# design.net
KiCad netlist of a schematic drawn in Altium Designer
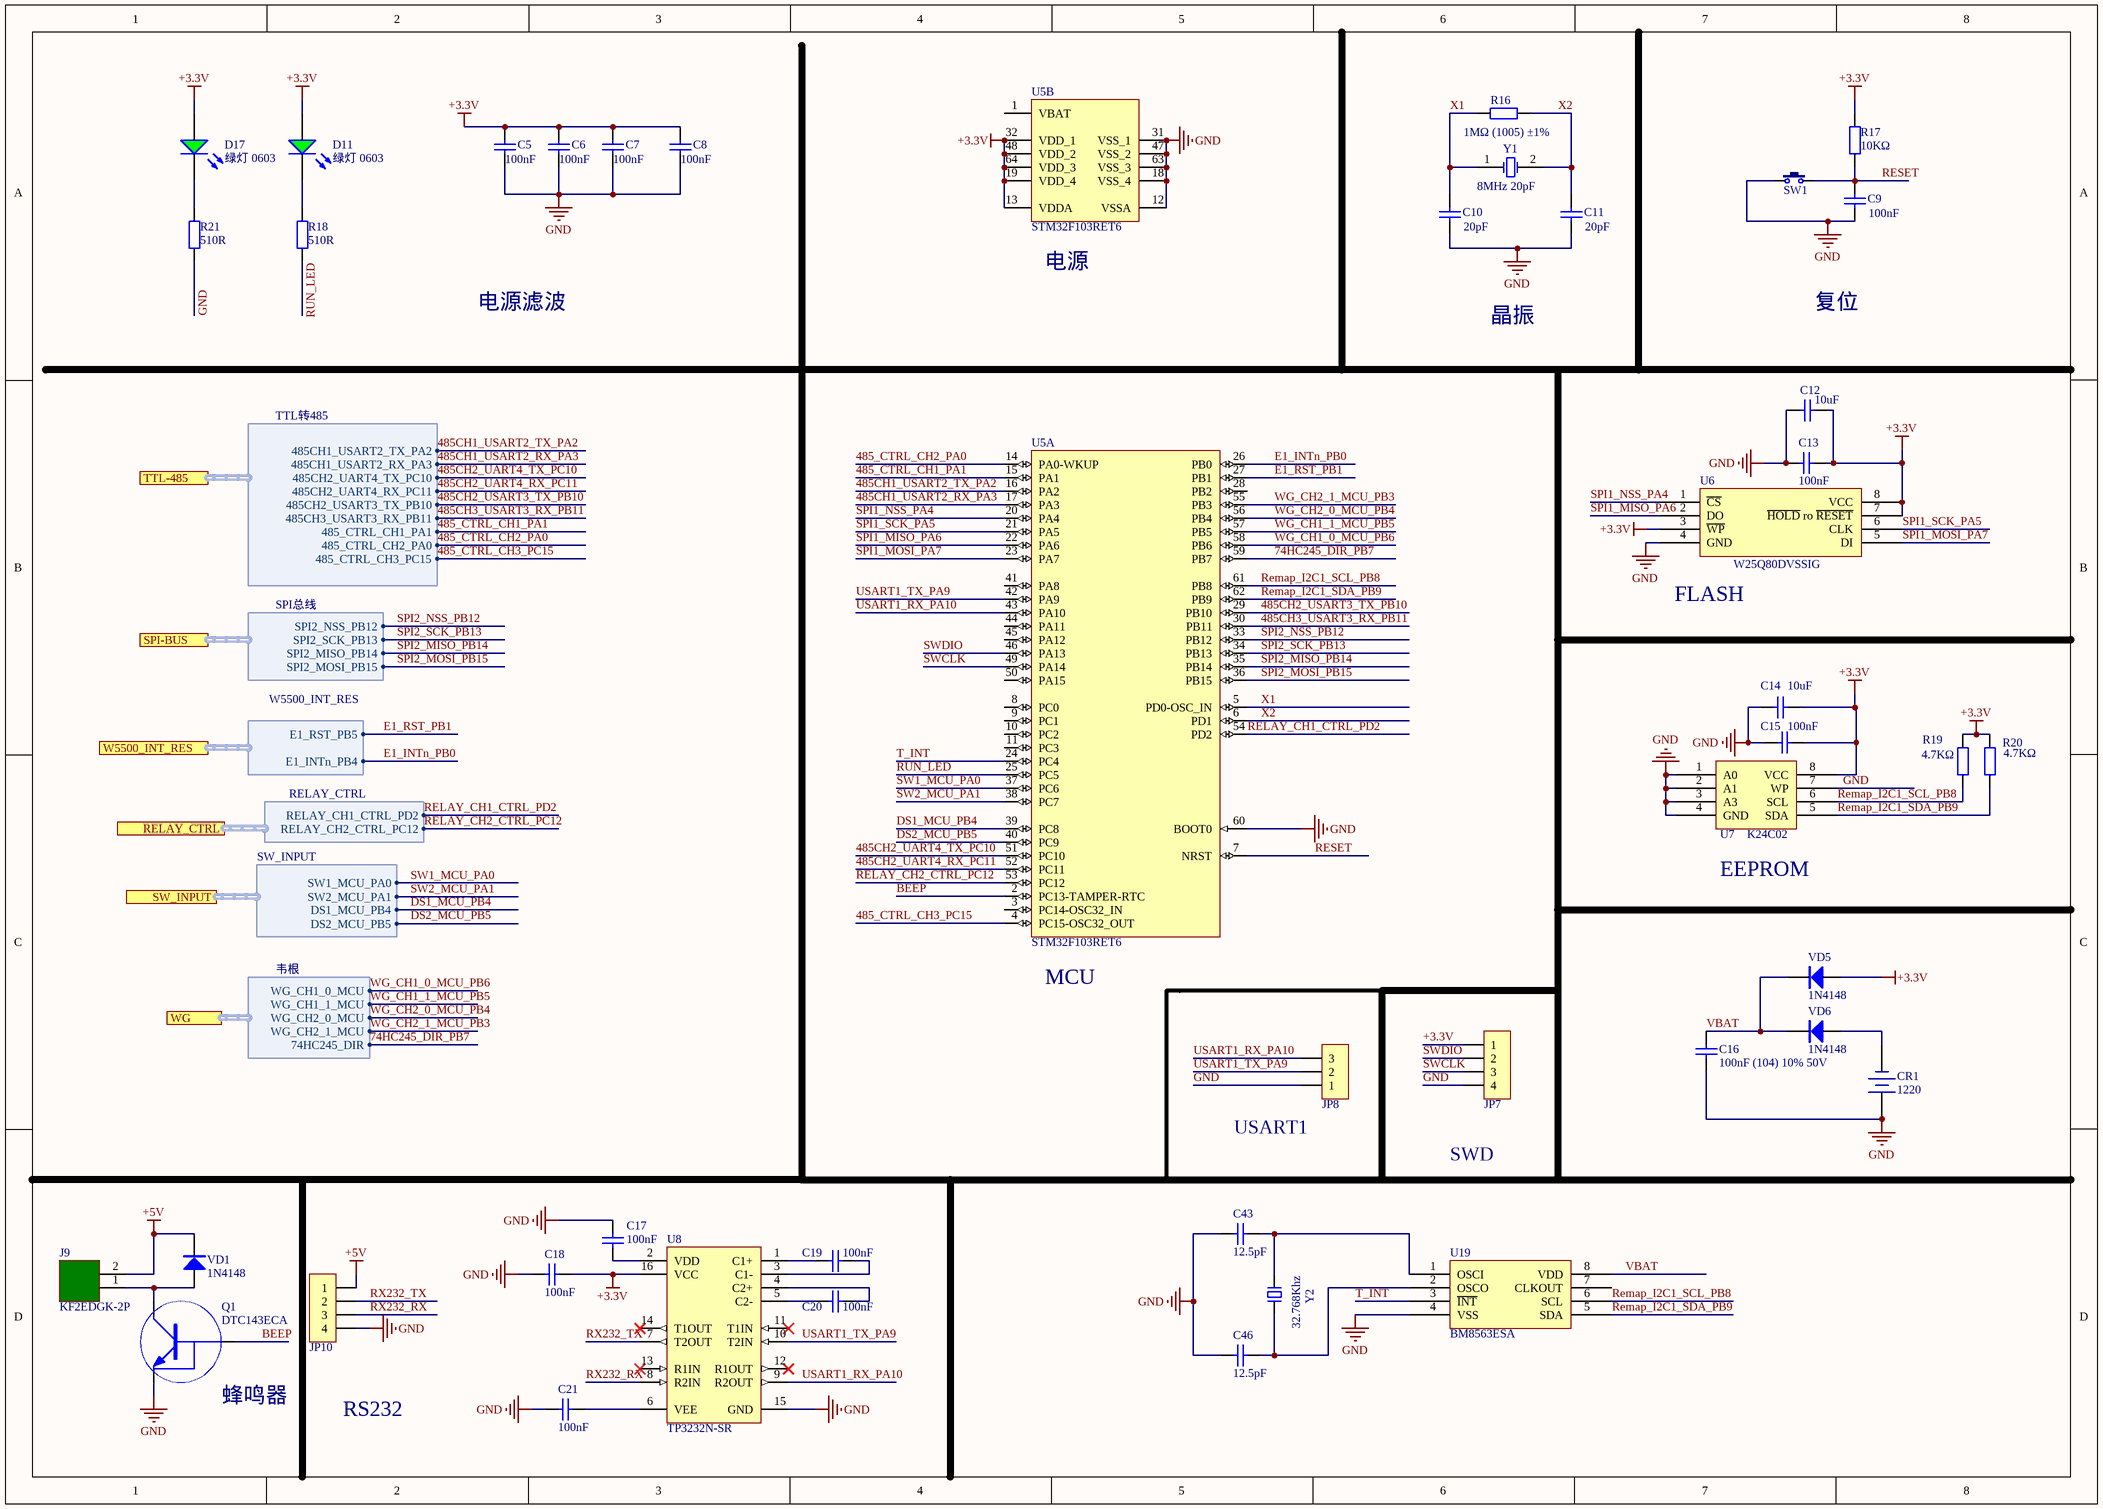
[diagram p0: 主控.SchDoc]

(export (version "E")
  (design (tool "Eeschema 10.0.6"))
  (components
    (comp (ref "C5")
      (value "100nF")
      (footprint "0603_C")
      (description "贴片电容")
      (libsource (lib "Miscellaneous Devices LC") (part "0603 100nF (104) 10% 50V"))
    )
    (comp (ref "C6")
      (value "100nF")
      (footprint "0603_C")
      (description "贴片电容")
      (libsource (lib "Miscellaneous Devices LC") (part "0603 100nF (104) 10% 50V"))
    )
    (comp (ref "C7")
      (value "100nF")
      (footprint "0603_C")
      (description "贴片电容")
      (libsource (lib "Miscellaneous Devices LC") (part "0603 100nF (104) 10% 50V"))
    )
    (comp (ref "C8")
      (value "100nF")
      (footprint "0603_C")
      (description "贴片电容")
      (libsource (lib "Miscellaneous Devices LC") (part "0603 100nF (104) 10% 50V"))
    )
    (comp (ref "C9")
      (value "100nF")
      (footprint "0603_C")
      (description "贴片电容")
      (libsource (lib "Miscellaneous Devices LC") (part "0603 100nF (104) 10% 50V"))
    )
    (comp (ref "C10")
      (value "20pF")
      (footprint "0603_C")
      (description "贴片电容")
      (libsource (lib "Miscellaneous Devices LC") (part "0603 6pF (6R0) 0.25pF 50V"))
    )
    (comp (ref "C11")
      (value "20pF")
      (footprint "0603_C")
      (description "贴片电容")
      (libsource (lib "Miscellaneous Devices LC") (part "0603 6pF (6R0) 0.25pF 50V"))
    )
    (comp (ref "C12")
      (value "10uF")
      (footprint "0603_C")
      (description "贴片电容")
      (libsource (lib "Miscellaneous Devices LC") (part "0603 10uF (106) 10% 10V"))
    )
    (comp (ref "C13")
      (value "100nF")
      (footprint "0603_C")
      (description "贴片电容")
      (libsource (lib "Miscellaneous Devices LC") (part "0603 100nF (104) 10% 50V"))
    )
    (comp (ref "C14")
      (value "10uF")
      (footprint "0603_C")
      (description "贴片电容")
      (libsource (lib "Miscellaneous Devices LC") (part "0603 10uF (106) 10% 10V"))
    )
    (comp (ref "C15")
      (value "100nF")
      (footprint "0603_C")
      (description "贴片电容")
      (libsource (lib "Miscellaneous Devices LC") (part "0603 100nF (104) 10% 50V"))
    )
    (comp (ref "C16")
      (value "100nF (104) 10% 50V")
      (footprint "0603_C")
      (description "贴片电容")
      (libsource (lib "Miscellaneous Devices LC") (part "0603 100nF (104) 10% 50V"))
    )
    (comp (ref "C17")
      (value "100nF")
      (footprint "0603_C")
      (description "贴片电容")
      (libsource (lib "Miscellaneous Devices LC") (part "0603 100nF (104) 10% 50V"))
    )
    (comp (ref "C18")
      (value "100nF")
      (footprint "0603_C")
      (description "贴片电容")
      (libsource (lib "Miscellaneous Devices LC") (part "0603 100nF (104) 10% 50V"))
    )
    (comp (ref "C19")
      (value "100nF")
      (footprint "0603_C")
      (description "贴片电容")
      (libsource (lib "Miscellaneous Devices LC") (part "0603 100nF (104) 10% 50V"))
    )
    (comp (ref "C20")
      (value "100nF")
      (footprint "0603_C")
      (description "贴片电容")
      (libsource (lib "Miscellaneous Devices LC") (part "0603 100nF (104) 10% 50V"))
    )
    (comp (ref "C21")
      (value "100nF")
      (footprint "0603_C")
      (description "贴片电容")
      (libsource (lib "Miscellaneous Devices LC") (part "0603 100nF (104) 10% 50V"))
    )
    (comp (ref "C43")
      (value "12.5pF")
      (footprint "0603_C")
      (description "贴片电容")
      (libsource (lib "Miscellaneous Devices LC") (part "0603 12pF (120) 5% 50V"))
    )
    (comp (ref "C46")
      (value "12.5pF")
      (footprint "0603_C")
      (description "贴片电容")
      (libsource (lib "Miscellaneous Devices LC") (part "0603 12pF (120) 5% 50V"))
    )
    (comp (ref "CR1")
      (value "1220")
      (footprint "CR1220_A")
      (description "微型电池")
      (fields (field (name "版权归属") "源创客"))
      (libsource (lib "源创客") (part "CR-3V"))
    )
    (comp (ref "D11")
      (value "绿灯 0603")
      (footprint "0603_LED_S1")
      (description "发光二极管")
      (libsource (lib "Miscellaneous Devices LC") (part "0603 绿灯"))
    )
    (comp (ref "D17")
      (value "绿灯 0603")
      (footprint "0603_LED_S1")
      (description "发光二极管")
      (libsource (lib "Miscellaneous Devices LC") (part "0603 绿灯"))
    )
    (comp (ref "J9")
      (value "KF2EDGK-2P")
      (footprint "KF2EDGK5.08W-2P")
      (libsource (lib "KF2EDGK") (part "KF2EDGK-2P"))
    )
    (comp (ref "JP7")
      (value "HDR-1X4")
      (footprint "HDR-1X4_H")
      (description "4P接插件")
      (fields (field (name "版权归属") "源创客"))
      (libsource (lib "") (part "Header 4_1"))
    )
    (comp (ref "JP8")
      (value "HDR-1X3")
      (footprint "HDR-1X3_H")
      (description "3P接插件")
      (fields (field (name "版权归属") "源创客"))
      (libsource (lib "源创客") (part "Header 3"))
    )
    (comp (ref "JP10")
      (value "HDR-1X4")
      (footprint "HDR-1X4")
      (description "4P接插件")
      (fields (field (name "版权归属") "源创客"))
      (libsource (lib "源创客") (part "Header 4"))
    )
    (comp (ref "Q1") (value "DTC143ECA") (description "NPN集成三极管") (libsource (lib "this") (part "DTC143ECA")))
    (comp (ref "R16")
      (value "1MΩ (1005) ±1%")
      (footprint "0603_R")
      (description "贴片电阻")
      (libsource (lib "Miscellaneous Devices LC") (part "0603 10MΩ (1005) 1%"))
    )
    (comp (ref "R17")
      (value "10KΩ")
      (footprint "0603_R")
      (description "贴片电阻")
      (libsource (lib "Miscellaneous Devices LC") (part "0603 10KΩ (1002) 1%"))
    )
    (comp (ref "R18")
      (value "510R")
      (footprint "0603_R")
      (description "贴片电阻")
      (libsource (lib "Miscellaneous Devices LC") (part "0603 2KΩ (2001) 1%"))
    )
    (comp (ref "R19")
      (value "4.7KΩ")
      (footprint "0603_R")
      (description "贴片电阻")
      (libsource (lib "Miscellaneous Devices LC") (part "0603 4.7KΩ (4701) 1%"))
    )
    (comp (ref "R20")
      (value "4.7KΩ")
      (footprint "0603_R")
      (description "贴片电阻")
      (libsource (lib "Miscellaneous Devices LC") (part "0603 4.7KΩ (4701) 1%"))
    )
    (comp (ref "R21")
      (value "510R")
      (footprint "0603_R")
      (description "贴片电阻")
      (libsource (lib "Miscellaneous Devices LC") (part "0603 2KΩ (2001) 1%"))
    )
    (comp (ref "SW1")
      (value "3x6x5")
      (footprint "TSW SMD-3*6*4.3")
      (description "3x6轻触开关")
      (fields (field (name "版权归属") "源创客"))
      (libsource (lib "源创客") (part "TSW 3x6"))
    )
    (comp (ref "U5")
      (value "STM32F103RET6")
      (footprint "LQFP-64_10x10x05P")
      (description "ARM")
      (libsource (lib "Miscellaneous Devices LC") (part "STM32F103RET6"))
    )
    (comp (ref "U6")
      (value "W25Q80DVSSIG")
      (footprint "SOIC-8_208mil")
      (description "Flash ROM")
      (libsource (lib "Miscellaneous Devices LC") (part "W25Q128FVSIG"))
    )
    (comp (ref "U7")
      (value "K24C02")
      (footprint "SOIC-8_150mil")
      (description "EEPROM")
      (libsource (lib "Miscellaneous Devices LC") (part "EEPROM/AT24C256C-SSHL-T"))
    )
    (comp (ref "U8")
      (value "TP3232N-SR")
      (footprint "SOIC-16_150mil")
      (description "RS232")
      (libsource (lib "Miscellaneous Devices LC") (part "MAX232ESE"))
    )
    (comp (ref "U19")
      (value "BM8563ESA")
      (footprint "SOIC-8_150mil")
      (description "实时时钟")
      (libsource (lib "Miscellaneous Devices LC") (part "PCF8563T/5,518"))
    )
    (comp (ref "VD1")
      (value "1N4148")
      (footprint "MINI_MELF (LL34)")
      (description "高速开关二极管")
      (fields (field (name "版权归属") "源创客"))
      (libsource (lib "源创客") (part "1N4148"))
    )
    (comp (ref "VD5")
      (value "1N4148")
      (footprint "MINI_MELF (LL34)")
      (description "高速开关二极管")
      (fields (field (name "版权归属") "源创客"))
      (libsource (lib "源创客") (part "1N4148"))
    )
    (comp (ref "VD6")
      (value "1N4148")
      (footprint "MINI_MELF (LL34)")
      (description "高速开关二极管")
      (fields (field (name "版权归属") "源创客"))
      (libsource (lib "源创客") (part "1N4148"))
    )
    (comp (ref "Y1")
      (value "8MHz 20pF")
      (footprint "XTAL-49S DIP")
      (description "贴片晶振")
      (libsource (lib "Miscellaneous Devices LC") (part "SMD-5032_2P 8MHz 20ppm 20pF"))
    )
    (comp (ref "Y2")
      (value "32.768Khz")
      (footprint "XTAL-3215")
      (description "2脚晶振")
      (fields (field (name "版权归属") "源创客"))
      (libsource (lib "源创客") (part "XTAL-2"))
    )
  )
  (nets
    (net (code "7") (name "+3.3V") (class "Default")
      (node (ref "C12") (pin "2") (pinfunction "2_2") (pintype "passive"))
      (node (ref "C13") (pin "1") (pinfunction "1_1") (pintype "passive"))
      (node (ref "C14") (pin "2") (pinfunction "2_2") (pintype "passive"))
      (node (ref "C15") (pin "1") (pinfunction "1_1") (pintype "passive"))
      (node (ref "C18") (pin "2") (pinfunction "2_2") (pintype "passive"))
      (node (ref "C5") (pin "2") (pinfunction "2_2") (pintype "passive"))
      (node (ref "C6") (pin "2") (pinfunction "2_2") (pintype "passive"))
      (node (ref "C7") (pin "2") (pinfunction "2_2") (pintype "passive"))
      (node (ref "C8") (pin "2") (pinfunction "2_2") (pintype "passive"))
      (node (ref "D11") (pin "A") (pinfunction "A_A") (pintype "passive"))
      (node (ref "D17") (pin "A") (pinfunction "A_A") (pintype "passive"))
      (node (ref "JP7") (pin "1") (pinfunction "1_1") (pintype "passive"))
      (node (ref "R17") (pin "1") (pinfunction "1_1") (pintype "passive"))
      (node (ref "R19") (pin "2") (pinfunction "2_2") (pintype "passive"))
      (node (ref "R20") (pin "2") (pinfunction "2_2") (pintype "passive"))
      (node (ref "U5") (pin "13") (pinfunction "VDDA_13") (pintype "power_in"))
      (node (ref "U5") (pin "19") (pinfunction "VDD_4_19") (pintype "power_in"))
      (node (ref "U5") (pin "32") (pinfunction "VDD_1_32") (pintype "power_in"))
      (node (ref "U5") (pin "48") (pinfunction "VDD_2_48") (pintype "power_in"))
      (node (ref "U5") (pin "64") (pinfunction "VDD_3_64") (pintype "power_in"))
      (node (ref "U6") (pin "3") (pinfunction "~{WP}_3") (pintype "passive"))
      (node (ref "U6") (pin "7") (pinfunction "~{HOLD}_ro_~{RESET}_7") (pintype "passive"))
      (node (ref "U6") (pin "8") (pinfunction "VCC_8") (pintype "passive"))
      (node (ref "U7") (pin "8") (pinfunction "VCC_8") (pintype "passive"))
      (node (ref "U8") (pin "16") (pinfunction "VCC_16") (pintype "power_in"))
      (node (ref "VD5") (pin "1") (pinfunction "A_1") (pintype "passive"))
    )
    (net (code "8") (name "+5V") (class "Default")
      (node (ref "J9") (pin "2") (pinfunction "2_2") (pintype "passive"))
      (node (ref "JP10") (pin "1") (pinfunction "1_1") (pintype "passive"))
      (node (ref "VD1") (pin "2") (pinfunction "K_2") (pintype "passive"))
    )
    (net (code "9") (name "/74HC245_DIR_PB7") (class "Default")
      (node (ref "U5") (pin "59") (pinfunction "PB7_59") (pintype "bidirectional"))
    )
    (net (code "10") (name "/485CH1_USART2_RX_PA3") (class "Default")
      (node (ref "U5") (pin "17") (pinfunction "PA3_17") (pintype "bidirectional"))
    )
    (net (code "11") (name "/485CH1_USART2_TX_PA2") (class "Default")
      (node (ref "U5") (pin "16") (pinfunction "PA2_16") (pintype "bidirectional"))
    )
    (net (code "12") (name "/485CH2_UART4_RX_PC11") (class "Default")
      (node (ref "U5") (pin "52") (pinfunction "PC11_52") (pintype "bidirectional"))
    )
    (net (code "13") (name "/485CH2_UART4_TX_PC10") (class "Default")
      (node (ref "U5") (pin "51") (pinfunction "PC10_51") (pintype "bidirectional"))
    )
    (net (code "14") (name "/485CH2_USART3_TX_PB10") (class "Default")
      (node (ref "U5") (pin "29") (pinfunction "PB10_29") (pintype "bidirectional"))
    )
    (net (code "15") (name "/485CH3_USART3_RX_PB11") (class "Default")
      (node (ref "U5") (pin "30") (pinfunction "PB11_30") (pintype "bidirectional"))
    )
    (net (code "16") (name "/485_CTRL_CH1_PA1") (class "Default")
      (node (ref "U5") (pin "15") (pinfunction "PA1_15") (pintype "bidirectional"))
    )
    (net (code "17") (name "/485_CTRL_CH2_PA0") (class "Default")
      (node (ref "U5") (pin "14") (pinfunction "PA0-WKUP_14") (pintype "bidirectional"))
    )
    (net (code "18") (name "/485_CTRL_CH3_PC15") (class "Default")
      (node (ref "U5") (pin "4") (pinfunction "PC15-OSC32_OUT_4") (pintype "bidirectional"))
    )
    (net (code "19") (name "/BEEP") (class "Default")
      (node (ref "Q1") (pin "1") (pinfunction "IN_1") (pintype "passive"))
      (node (ref "U5") (pin "2") (pinfunction "PC13-TAMPER-RTC_2") (pintype "bidirectional"))
    )
    (net (code "20") (name "/DS1_MCU_PB4") (class "Default")
      (node (ref "U5") (pin "39") (pinfunction "PC8_39") (pintype "bidirectional"))
    )
    (net (code "21") (name "/DS2_MCU_PB5") (class "Default")
      (node (ref "U5") (pin "40") (pinfunction "PC9_40") (pintype "bidirectional"))
    )
    (net (code "22") (name "/E1_INTn_PB0") (class "Default")
      (node (ref "U5") (pin "26") (pinfunction "PB0_26") (pintype "bidirectional"))
    )
    (net (code "23") (name "/E1_RST_PB1") (class "Default")
      (node (ref "U5") (pin "27") (pinfunction "PB1_27") (pintype "bidirectional"))
    )
    (net (code "24") (name "/RELAY_CH1_CTRL_PD2") (class "Default")
      (node (ref "U5") (pin "54") (pinfunction "PD2_54") (pintype "bidirectional"))
    )
    (net (code "25") (name "/RELAY_CH2_CTRL_PC12") (class "Default")
      (node (ref "U5") (pin "53") (pinfunction "PC12_53") (pintype "bidirectional"))
    )
    (net (code "26") (name "/RESET") (class "Default")
      (node (ref "C9") (pin "2") (pinfunction "2_2") (pintype "passive"))
      (node (ref "R17") (pin "2") (pinfunction "2_2") (pintype "passive"))
      (node (ref "SW1") (pin "2") (pinfunction "2_2") (pintype "passive"))
      (node (ref "U5") (pin "7") (pinfunction "NRST_7") (pintype "bidirectional"))
    )
    (net (code "27") (name "/RUN_LED") (class "Default")
      (node (ref "R18") (pin "1") (pinfunction "1_1") (pintype "passive"))
      (node (ref "U5") (pin "25") (pinfunction "PC5_25") (pintype "bidirectional"))
    )
    (net (code "28") (name "/RX232_RX") (class "Default")
      (node (ref "JP10") (pin "3") (pinfunction "3_3") (pintype "passive"))
      (node (ref "U8") (pin "8") (pinfunction "R2IN_8") (pintype "input"))
    )
    (net (code "29") (name "/RX232_TX") (class "Default")
      (node (ref "JP10") (pin "2") (pinfunction "2_2") (pintype "passive"))
      (node (ref "U8") (pin "7") (pinfunction "T2OUT_7") (pintype "output"))
    )
    (net (code "30") (name "/Remap_I2C1_SCL_PB8") (class "Default")
      (node (ref "R19") (pin "1") (pinfunction "1_1") (pintype "passive"))
      (node (ref "U19") (pin "6") (pinfunction "SCL_6") (pintype "passive"))
      (node (ref "U5") (pin "61") (pinfunction "PB8_61") (pintype "bidirectional"))
      (node (ref "U7") (pin "6") (pinfunction "SCL_6") (pintype "passive"))
    )
    (net (code "31") (name "/Remap_I2C1_SDA_PB9") (class "Default")
      (node (ref "R20") (pin "1") (pinfunction "1_1") (pintype "passive"))
      (node (ref "U19") (pin "5") (pinfunction "SDA_5") (pintype "passive"))
      (node (ref "U5") (pin "62") (pinfunction "PB9_62") (pintype "bidirectional"))
      (node (ref "U7") (pin "5") (pinfunction "SDA_5") (pintype "passive"))
    )
    (net (code "32") (name "/SPI1_MISO_PA6") (class "Default")
      (node (ref "U5") (pin "22") (pinfunction "PA6_22") (pintype "bidirectional"))
      (node (ref "U6") (pin "2") (pinfunction "DO_2") (pintype "passive"))
    )
    (net (code "33") (name "/SPI1_MOSI_PA7") (class "Default")
      (node (ref "U5") (pin "23") (pinfunction "PA7_23") (pintype "bidirectional"))
      (node (ref "U6") (pin "5") (pinfunction "DI_5") (pintype "passive"))
    )
    (net (code "34") (name "/SPI1_NSS_PA4") (class "Default")
      (node (ref "U5") (pin "20") (pinfunction "PA4_20") (pintype "bidirectional"))
      (node (ref "U6") (pin "1") (pinfunction "~{CS}_1") (pintype "passive"))
    )
    (net (code "35") (name "/SPI1_SCK_PA5") (class "Default")
      (node (ref "U5") (pin "21") (pinfunction "PA5_21") (pintype "bidirectional"))
      (node (ref "U6") (pin "6") (pinfunction "CLK_6") (pintype "passive"))
    )
    (net (code "36") (name "/SPI2_MISO_PB14") (class "Default")
      (node (ref "U5") (pin "35") (pinfunction "PB14_35") (pintype "bidirectional"))
    )
    (net (code "37") (name "/SPI2_MOSI_PB15") (class "Default")
      (node (ref "U5") (pin "36") (pinfunction "PB15_36") (pintype "bidirectional"))
    )
    (net (code "38") (name "/SPI2_NSS_PB12") (class "Default")
      (node (ref "U5") (pin "33") (pinfunction "PB12_33") (pintype "bidirectional"))
    )
    (net (code "39") (name "/SPI2_SCK_PB13") (class "Default")
      (node (ref "U5") (pin "34") (pinfunction "PB13_34") (pintype "bidirectional"))
    )
    (net (code "40") (name "/SW1_MCU_PA0") (class "Default")
      (node (ref "U5") (pin "37") (pinfunction "PC6_37") (pintype "bidirectional"))
    )
    (net (code "41") (name "/SW2_MCU_PA1") (class "Default")
      (node (ref "U5") (pin "38") (pinfunction "PC7_38") (pintype "bidirectional"))
    )
    (net (code "42") (name "/SWCLK") (class "Default")
      (node (ref "JP7") (pin "3") (pinfunction "3_3") (pintype "passive"))
      (node (ref "U5") (pin "49") (pinfunction "PA14_49") (pintype "bidirectional"))
    )
    (net (code "43") (name "/SWDIO") (class "Default")
      (node (ref "JP7") (pin "2") (pinfunction "2_2") (pintype "passive"))
      (node (ref "U5") (pin "46") (pinfunction "PA13_46") (pintype "bidirectional"))
    )
    (net (code "44") (name "/T_INT") (class "Default")
      (node (ref "U19") (pin "3") (pinfunction "~{INT}_3") (pintype "passive"))
      (node (ref "U5") (pin "24") (pinfunction "PC4_24") (pintype "bidirectional"))
    )
    (net (code "45") (name "/USART1_RX_PA10") (class "Default")
      (node (ref "JP8") (pin "3") (pinfunction "3_3") (pintype "passive"))
      (node (ref "U5") (pin "43") (pinfunction "PA10_43") (pintype "bidirectional"))
      (node (ref "U8") (pin "9") (pinfunction "R2OUT_9") (pintype "output"))
    )
    (net (code "46") (name "/USART1_TX_PA9") (class "Default")
      (node (ref "JP8") (pin "2") (pinfunction "2_2") (pintype "passive"))
      (node (ref "U5") (pin "42") (pinfunction "PA9_42") (pintype "bidirectional"))
      (node (ref "U8") (pin "10") (pinfunction "T2IN_10") (pintype "input"))
    )
    (net (code "47") (name "/VBAT") (class "Default")
      (node (ref "C16") (pin "2") (pinfunction "2_2") (pintype "passive"))
      (node (ref "U19") (pin "8") (pinfunction "VDD_8") (pintype "passive"))
      (node (ref "VD5") (pin "2") (pinfunction "K_2") (pintype "passive"))
      (node (ref "VD6") (pin "2") (pinfunction "K_2") (pintype "passive"))
    )
    (net (code "48") (name "/WG_CH1_0_MCU_PB6") (class "Default")
      (node (ref "U5") (pin "58") (pinfunction "PB6_58") (pintype "bidirectional"))
    )
    (net (code "49") (name "/WG_CH1_1_MCU_PB5") (class "Default")
      (node (ref "U5") (pin "57") (pinfunction "PB5_57") (pintype "bidirectional"))
    )
    (net (code "50") (name "/WG_CH2_0_MCU_PB4") (class "Default")
      (node (ref "U5") (pin "56") (pinfunction "PB4_56") (pintype "bidirectional"))
    )
    (net (code "51") (name "/WG_CH2_1_MCU_PB3") (class "Default")
      (node (ref "U5") (pin "55") (pinfunction "PB3_55") (pintype "bidirectional"))
    )
    (net (code "52") (name "/X1") (class "Default")
      (node (ref "C10") (pin "2") (pinfunction "2_2") (pintype "passive"))
      (node (ref "R16") (pin "1") (pinfunction "1_1") (pintype "passive"))
      (node (ref "U5") (pin "5") (pinfunction "PD0-OSC_IN_5") (pintype "bidirectional"))
      (node (ref "Y1") (pin "1") (pinfunction "OSC1_1") (pintype "passive"))
    )
    (net (code "53") (name "/X2") (class "Default")
      (node (ref "C11") (pin "2") (pinfunction "2_2") (pintype "passive"))
      (node (ref "R16") (pin "2") (pinfunction "2_2") (pintype "passive"))
      (node (ref "U5") (pin "6") (pinfunction "PD1_6") (pintype "bidirectional"))
      (node (ref "Y1") (pin "2") (pinfunction "OSC2_2") (pintype "passive"))
    )
    (net (code "60") (name "GND") (class "Default")
      (node (ref "C10") (pin "1") (pinfunction "1_1") (pintype "passive"))
      (node (ref "C11") (pin "1") (pinfunction "1_1") (pintype "passive"))
      (node (ref "C12") (pin "1") (pinfunction "1_1") (pintype "passive"))
      (node (ref "C13") (pin "2") (pinfunction "2_2") (pintype "passive"))
      (node (ref "C14") (pin "1") (pinfunction "1_1") (pintype "passive"))
      (node (ref "C15") (pin "2") (pinfunction "2_2") (pintype "passive"))
      (node (ref "C16") (pin "1") (pinfunction "1_1") (pintype "passive"))
      (node (ref "C17") (pin "2") (pinfunction "2_2") (pintype "passive"))
      (node (ref "C18") (pin "1") (pinfunction "1_1") (pintype "passive"))
      (node (ref "C21") (pin "1") (pinfunction "1_1") (pintype "passive"))
      (node (ref "C43") (pin "1") (pinfunction "1_1") (pintype "passive"))
      (node (ref "C46") (pin "1") (pinfunction "1_1") (pintype "passive"))
      (node (ref "C5") (pin "1") (pinfunction "1_1") (pintype "passive"))
      (node (ref "C6") (pin "1") (pinfunction "1_1") (pintype "passive"))
      (node (ref "C7") (pin "1") (pinfunction "1_1") (pintype "passive"))
      (node (ref "C8") (pin "1") (pinfunction "1_1") (pintype "passive"))
      (node (ref "C9") (pin "1") (pinfunction "1_1") (pintype "passive"))
      (node (ref "CR1") (pin "1") (pinfunction "DC+_1") (pintype "passive"))
      (node (ref "JP10") (pin "4") (pinfunction "4_4") (pintype "passive"))
      (node (ref "JP7") (pin "4") (pinfunction "4_4") (pintype "passive"))
      (node (ref "JP8") (pin "1") (pinfunction "1_1") (pintype "passive"))
      (node (ref "Q1") (pin "2") (pinfunction "GND_2") (pintype "passive"))
      (node (ref "R21") (pin "1") (pinfunction "1_1") (pintype "passive"))
      (node (ref "SW1") (pin "1") (pinfunction "1_1") (pintype "passive"))
      (node (ref "U19") (pin "4") (pinfunction "VSS_4") (pintype "passive"))
      (node (ref "U5") (pin "12") (pinfunction "VSSA_12") (pintype "power_in"))
      (node (ref "U5") (pin "18") (pinfunction "VSS_4_18") (pintype "power_in"))
      (node (ref "U5") (pin "31") (pinfunction "VSS_1_31") (pintype "power_in"))
      (node (ref "U5") (pin "47") (pinfunction "VSS_2_47") (pintype "power_in"))
      (node (ref "U5") (pin "60") (pinfunction "BOOT0_60") (pintype "input"))
      (node (ref "U5") (pin "63") (pinfunction "VSS_3_63") (pintype "power_in"))
      (node (ref "U6") (pin "4") (pinfunction "GND_4") (pintype "passive"))
      (node (ref "U7") (pin "1") (pinfunction "A0_1") (pintype "passive"))
      (node (ref "U7") (pin "2") (pinfunction "A1_2") (pintype "passive"))
      (node (ref "U7") (pin "3") (pinfunction "A3_3") (pintype "passive"))
      (node (ref "U7") (pin "4") (pinfunction "GND_4") (pintype "passive"))
      (node (ref "U7") (pin "7") (pinfunction "WP_7") (pintype "passive"))
      (node (ref "U8") (pin "15") (pinfunction "GND_15") (pintype "power_in"))
    )
    (net (code "61") (name "Net-(CR1-DC-)") (class "Default")
      (node (ref "CR1") (pin "2") (pinfunction "DC-_2") (pintype "passive"))
      (node (ref "VD6") (pin "1") (pinfunction "A_1") (pintype "passive"))
    )
    (net (code "62") (name "Net-(D11-PadK)") (class "Default")
      (node (ref "D11") (pin "K") (pinfunction "K_K") (pintype "passive"))
      (node (ref "R18") (pin "2") (pinfunction "2_2") (pintype "passive"))
    )
    (net (code "63") (name "Net-(D17-PadK)") (class "Default")
      (node (ref "D17") (pin "K") (pinfunction "K_K") (pintype "passive"))
      (node (ref "R21") (pin "2") (pinfunction "2_2") (pintype "passive"))
    )
    (net (code "64") (name "Net-(Q1-OUT)") (class "Default")
      (node (ref "J9") (pin "1") (pinfunction "1_1") (pintype "passive"))
      (node (ref "Q1") (pin "3") (pinfunction "OUT_3") (pintype "passive"))
      (node (ref "VD1") (pin "1") (pinfunction "A_1") (pintype "passive"))
    )
    (net (code "65") (name "Net-(U8-C1+)") (class "Default")
      (node (ref "C19") (pin "1") (pinfunction "1_1") (pintype "passive"))
      (node (ref "U8") (pin "1") (pinfunction "C1+_1") (pintype "passive"))
    )
    (net (code "66") (name "Net-(U8-C1-)") (class "Default")
      (node (ref "C19") (pin "2") (pinfunction "2_2") (pintype "passive"))
      (node (ref "U8") (pin "3") (pinfunction "C1-_3") (pintype "passive"))
    )
    (net (code "67") (name "Net-(U8-C2+)") (class "Default")
      (node (ref "C20") (pin "2") (pinfunction "2_2") (pintype "passive"))
      (node (ref "U8") (pin "4") (pinfunction "C2+_4") (pintype "passive"))
    )
    (net (code "68") (name "Net-(U8-C2-)") (class "Default")
      (node (ref "C20") (pin "1") (pinfunction "1_1") (pintype "passive"))
      (node (ref "U8") (pin "5") (pinfunction "C2-_5") (pintype "passive"))
    )
    (net (code "69") (name "Net-(U8-VDD)") (class "Default")
      (node (ref "C17") (pin "1") (pinfunction "1_1") (pintype "passive"))
      (node (ref "U8") (pin "2") (pinfunction "VDD_2") (pintype "power_in"))
    )
    (net (code "70") (name "Net-(U8-VEE)") (class "Default")
      (node (ref "C21") (pin "2") (pinfunction "2_2") (pintype "passive"))
      (node (ref "U8") (pin "6") (pinfunction "VEE_6") (pintype "power_in"))
    )
    (net (code "71") (name "Net-(U19-OSCI)") (class "Default")
      (node (ref "C43") (pin "2") (pinfunction "2_2") (pintype "passive"))
      (node (ref "U19") (pin "1") (pinfunction "OSCI_1") (pintype "passive"))
      (node (ref "Y2") (pin "1") (pinfunction "1_1") (pintype "passive"))
    )
    (net (code "72") (name "Net-(U19-OSCO)") (class "Default")
      (node (ref "C46") (pin "2") (pinfunction "2_2") (pintype "passive"))
      (node (ref "U19") (pin "2") (pinfunction "OSCO_2") (pintype "passive"))
      (node (ref "Y2") (pin "2") (pinfunction "2_2") (pintype "passive"))
    )
    (net (code "73") (name "unconnected-(U5A-PA8-Pad41)") (class "Default")
      (node (ref "U5") (pin "41") (pinfunction "PA8_41") (pintype "bidirectional"))
    )
    (net (code "74") (name "unconnected-(U5A-PA11-Pad44)") (class "Default")
      (node (ref "U5") (pin "44") (pinfunction "PA11_44") (pintype "bidirectional"))
    )
    (net (code "75") (name "unconnected-(U5A-PA12-Pad45)") (class "Default")
      (node (ref "U5") (pin "45") (pinfunction "PA12_45") (pintype "bidirectional"))
    )
    (net (code "76") (name "unconnected-(U5A-PA15-Pad50)") (class "Default")
      (node (ref "U5") (pin "50") (pinfunction "PA15_50") (pintype "bidirectional"))
    )
    (net (code "77") (name "unconnected-(U5A-PB2-Pad28)") (class "Default")
      (node (ref "U5") (pin "28") (pinfunction "PB2_28") (pintype "bidirectional"))
    )
    (net (code "78") (name "unconnected-(U5A-PC0-Pad8)") (class "Default")
      (node (ref "U5") (pin "8") (pinfunction "PC0_8") (pintype "bidirectional"))
    )
    (net (code "79") (name "unconnected-(U5A-PC1-Pad9)") (class "Default")
      (node (ref "U5") (pin "9") (pinfunction "PC1_9") (pintype "bidirectional"))
    )
    (net (code "80") (name "unconnected-(U5A-PC2-Pad10)") (class "Default")
      (node (ref "U5") (pin "10") (pinfunction "PC2_10") (pintype "bidirectional"))
    )
    (net (code "81") (name "unconnected-(U5A-PC3-Pad11)") (class "Default")
      (node (ref "U5") (pin "11") (pinfunction "PC3_11") (pintype "bidirectional"))
    )
    (net (code "82") (name "unconnected-(U5A-PC14-OSC32_IN-Pad3)") (class "Default")
      (node (ref "U5") (pin "3") (pinfunction "PC14-OSC32_IN_3") (pintype "bidirectional"))
    )
    (net (code "83") (name "unconnected-(U5B-VBAT-Pad1)") (class "Default")
      (node (ref "U5") (pin "1") (pinfunction "VBAT_1") (pintype "power_in"))
    )
    (net (code "84") (name "unconnected-(U8-R1IN-Pad13)") (class "Default")
      (node (ref "U8") (pin "13") (pinfunction "R1IN_13") (pintype "input+no_connect"))
    )
    (net (code "85") (name "unconnected-(U8-R1OUT-Pad12)") (class "Default")
      (node (ref "U8") (pin "12") (pinfunction "R1OUT_12") (pintype "output+no_connect"))
    )
    (net (code "86") (name "unconnected-(U8-T1IN-Pad11)") (class "Default")
      (node (ref "U8") (pin "11") (pinfunction "T1IN_11") (pintype "input+no_connect"))
    )
    (net (code "87") (name "unconnected-(U8-T1OUT-Pad14)") (class "Default")
      (node (ref "U8") (pin "14") (pinfunction "T1OUT_14") (pintype "output+no_connect"))
    )
    (net (code "88") (name "unconnected-(U19-CLKOUT-Pad7)") (class "Default")
      (node (ref "U19") (pin "7") (pinfunction "CLKOUT_7") (pintype "passive"))
    )
  )
)
